# Connectors.net
KiCad netlist of a schematic drawn in Altium Designer
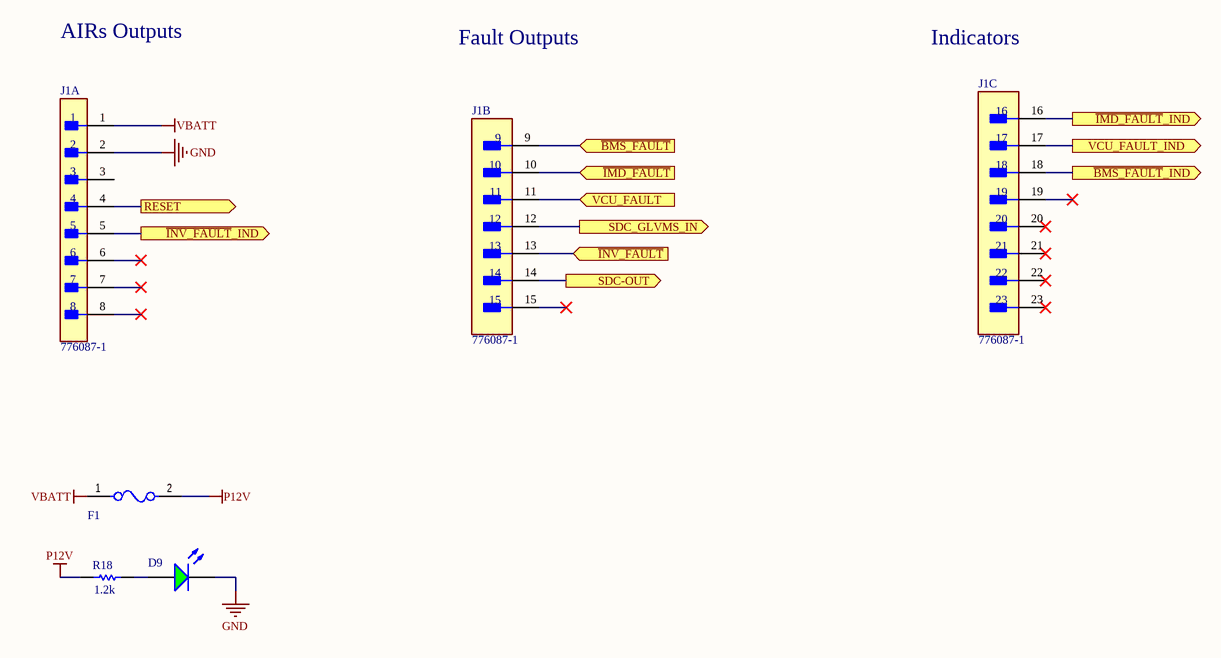
[diagram p0:  Connectors.SchDoc]

(export (version "E")
  (design (tool "Eeschema 10.0.6"))
  (components
    (comp (ref "D9")
      (value "597-3311-407F")
      (footprint "DIAL-597-3311-407F_V")
      (description "LED Green, 75 mW, 30 mA, -30 to 85 degC, 2-Pin SMD, RoHS, Tape and Reel")
      (fields (field (name "MANUFACTURER") "Dialight"))
      (libsource (lib "Altium Content Vault") (part "LED-GREEN-AK-2"))
    )
    (comp (ref "F1")
      (value "0468001.NRHF")
      (footprint "FP-437-MFG")
      (description "FUSE BRD MNT 1A 32VAC 35VDC 1206")
      (fields
        (field (name "OCTOPART") "https://octopart.com/0437003.wr-littelfuse-8600121")
        (field (name "MANUFACTURER") "Littelfuse Inc")
      )
      (libsource (lib "Altium Content Vault") (part "5bcf9b9f640e542cf0359d10258e979"))
    )
    (comp (ref "J1")
      (value "776087-1")
      (footprint "FP-776087-1-MFG")
      (description "CONN HEADER R/A 23POS 4MM")
      (libsource (lib "Altium Content Vault") (part "1cdbe6524175775e54446a79a4f0ed8"))
    )
    (comp (ref "R18")
      (value "1.2k")
      (footprint "RESC3216X70X50LL05T20")
      (description "ERJ8ENF1201V")
      (fields (field (name "MANUFACTURER") "Panasonic"))
      (libsource (lib "Altium Content Vault") (part "RES"))
    )
  )
  (nets
    (net (code "1") (name "/RESET") (class "Default")
      (node (ref "J1") (pin "4") (pinfunction "4_4") (pintype "passive"))
    )
    (net (code "2") (name "/SDC-OUT") (class "Default")
      (node (ref "J1") (pin "14") (pinfunction "14_14") (pintype "passive"))
    )
    (net (code "3") (name "/SDC_GLVMS_IN") (class "Default")
      (node (ref "J1") (pin "12") (pinfunction "12_12") (pintype "passive"))
    )
    (net (code "4") (name "/VCU_FAULT") (class "Default")
      (node (ref "J1") (pin "11") (pinfunction "11_11") (pintype "passive"))
    )
    (net (code "5") (name "/VCU_FAULT_IND") (class "Default")
      (node (ref "J1") (pin "17") (pinfunction "17_17") (pintype "passive"))
    )
    (net (code "6") (name "/~{BMS_FAULT}") (class "Default")
      (node (ref "J1") (pin "9") (pinfunction "9_9") (pintype "passive"))
    )
    (net (code "7") (name "/~{BMS_FAULT}_IND") (class "Default")
      (node (ref "J1") (pin "18") (pinfunction "18_18") (pintype "passive"))
    )
    (net (code "8") (name "/~{IMD_FAULT}") (class "Default")
      (node (ref "J1") (pin "10") (pinfunction "10_10") (pintype "passive"))
    )
    (net (code "9") (name "/~{IMD_FAULT}_IND") (class "Default")
      (node (ref "J1") (pin "16") (pinfunction "16_16") (pintype "passive"))
    )
    (net (code "10") (name "/~{INV_FAULT}") (class "Default")
      (node (ref "J1") (pin "13") (pinfunction "13_13") (pintype "passive"))
    )
    (net (code "11") (name "/~{INV_FAULT}_IND") (class "Default")
      (node (ref "J1") (pin "5") (pinfunction "5_5") (pintype "passive"))
    )
    (net (code "12") (name "GND") (class "Default")
      (node (ref "D9") (pin "2") (pinfunction "K_2") (pintype "passive"))
      (node (ref "J1") (pin "2") (pinfunction "2_2") (pintype "passive"))
    )
    (net (code "13") (name "Net-(D9-A)") (class "Default")
      (node (ref "D9") (pin "1") (pinfunction "A_1") (pintype "passive"))
      (node (ref "R18") (pin "2") (pinfunction "2_2") (pintype "passive"))
    )
    (net (code "14") (name "P12V") (class "Default")
      (node (ref "F1") (pin "2") (pinfunction "2_2") (pintype "passive"))
      (node (ref "R18") (pin "1") (pinfunction "1_1") (pintype "passive"))
    )
    (net (code "15") (name "VBATT") (class "Default")
      (node (ref "F1") (pin "1") (pinfunction "1_1") (pintype "passive"))
      (node (ref "J1") (pin "1") (pinfunction "1_1") (pintype "passive"))
    )
    (net (code "16") (name "unconnected-(J1-Pad3)") (class "Default")
      (node (ref "J1") (pin "3") (pinfunction "3_3") (pintype "passive"))
    )
    (net (code "17") (name "unconnected-(J1-Pad6)") (class "Default")
      (node (ref "J1") (pin "6") (pinfunction "6_6") (pintype "passive+no_connect"))
    )
    (net (code "18") (name "unconnected-(J1-Pad7)") (class "Default")
      (node (ref "J1") (pin "7") (pinfunction "7_7") (pintype "passive+no_connect"))
    )
    (net (code "19") (name "unconnected-(J1-Pad8)") (class "Default")
      (node (ref "J1") (pin "8") (pinfunction "8_8") (pintype "passive+no_connect"))
    )
    (net (code "20") (name "unconnected-(J1-Pad15)") (class "Default")
      (node (ref "J1") (pin "15") (pinfunction "15_15") (pintype "passive+no_connect"))
    )
    (net (code "21") (name "unconnected-(J1-Pad19)") (class "Default")
      (node (ref "J1") (pin "19") (pinfunction "19_19") (pintype "passive+no_connect"))
    )
    (net (code "22") (name "unconnected-(J1-Pad20)") (class "Default")
      (node (ref "J1") (pin "20") (pinfunction "20_20") (pintype "passive+no_connect"))
    )
    (net (code "23") (name "unconnected-(J1-Pad21)") (class "Default")
      (node (ref "J1") (pin "21") (pinfunction "21_21") (pintype "passive+no_connect"))
    )
    (net (code "24") (name "unconnected-(J1-Pad22)") (class "Default")
      (node (ref "J1") (pin "22") (pinfunction "22_22") (pintype "passive+no_connect"))
    )
    (net (code "25") (name "unconnected-(J1-Pad23)") (class "Default")
      (node (ref "J1") (pin "23") (pinfunction "23_23") (pintype "passive+no_connect"))
    )
  )
)
